# design.net
KiCad netlist of a schematic drawn in Altium Designer
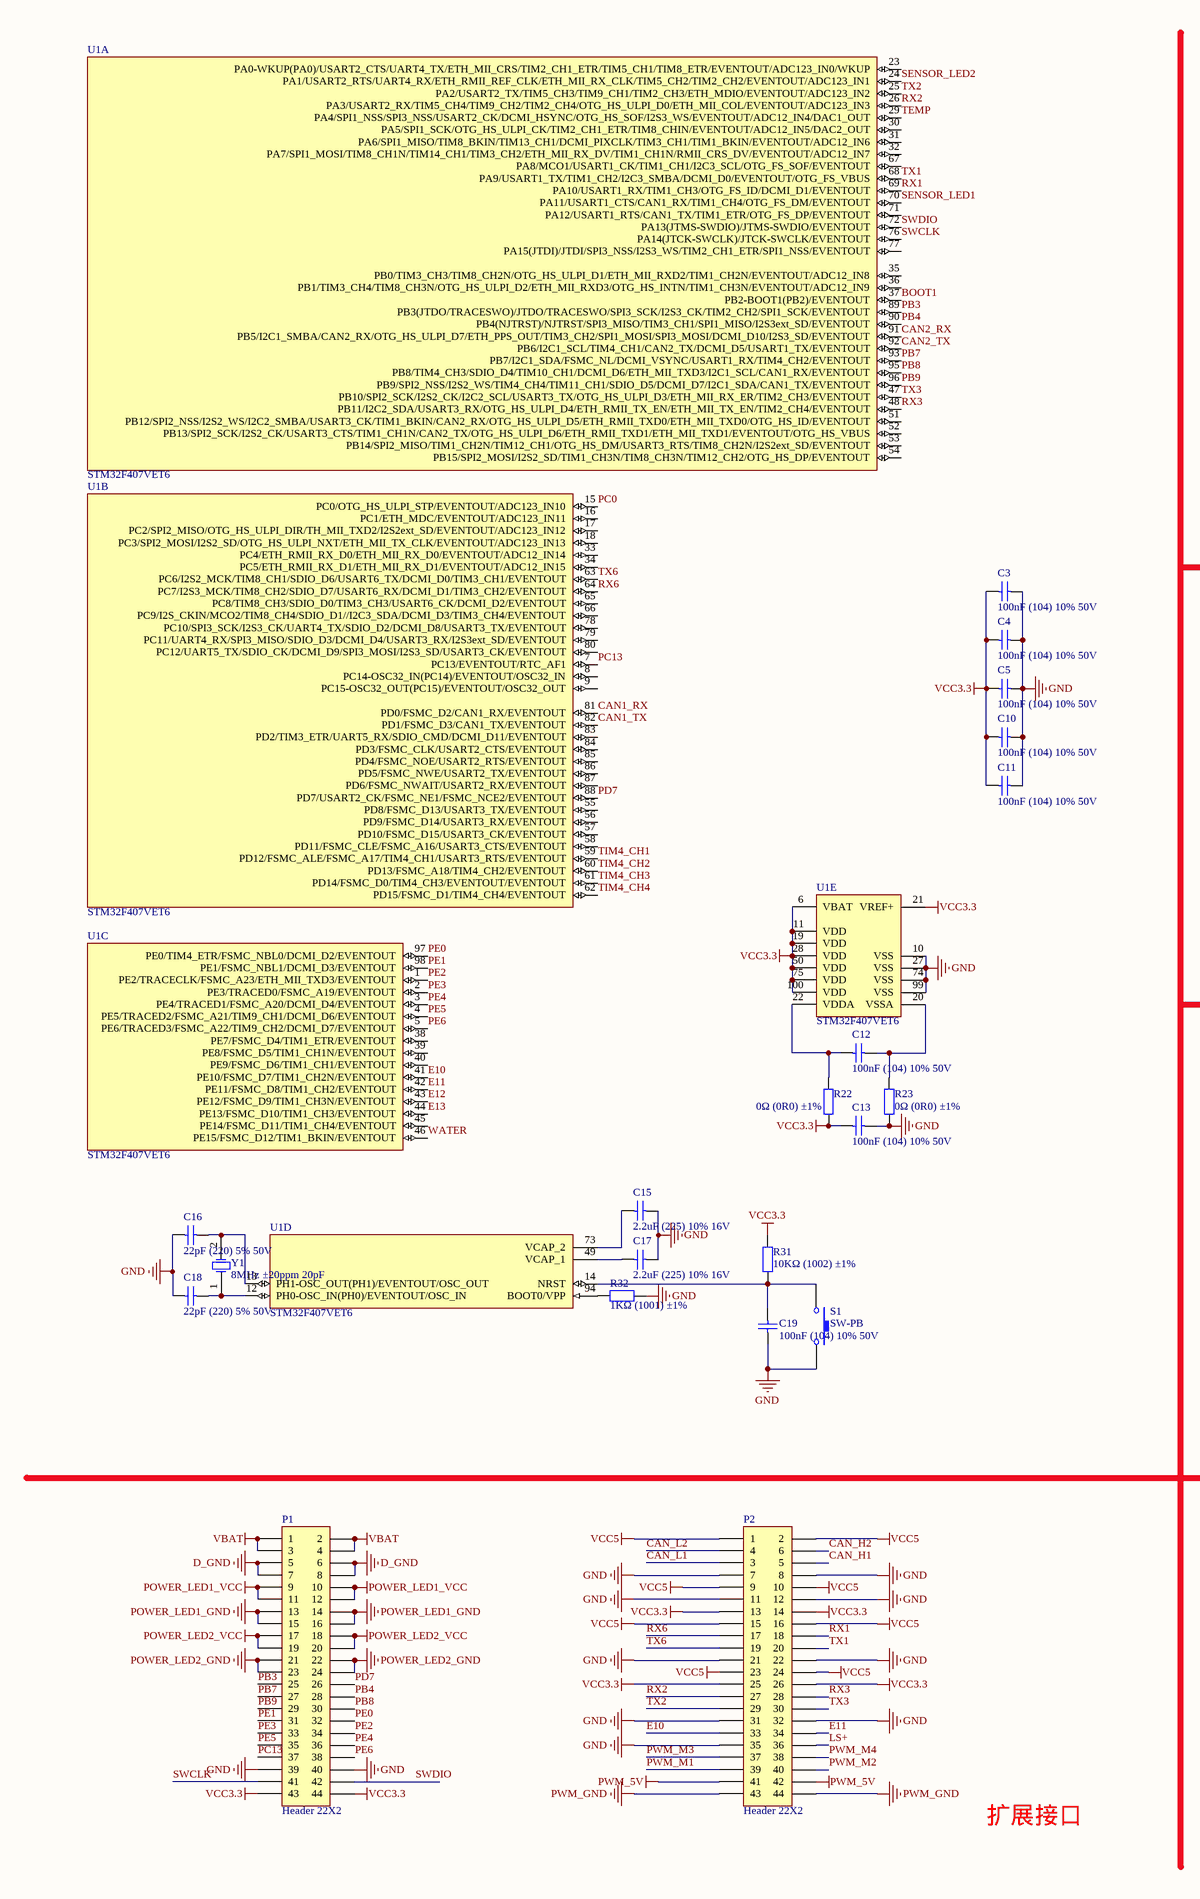
[diagram p0: 主控板.SchDoc, left]
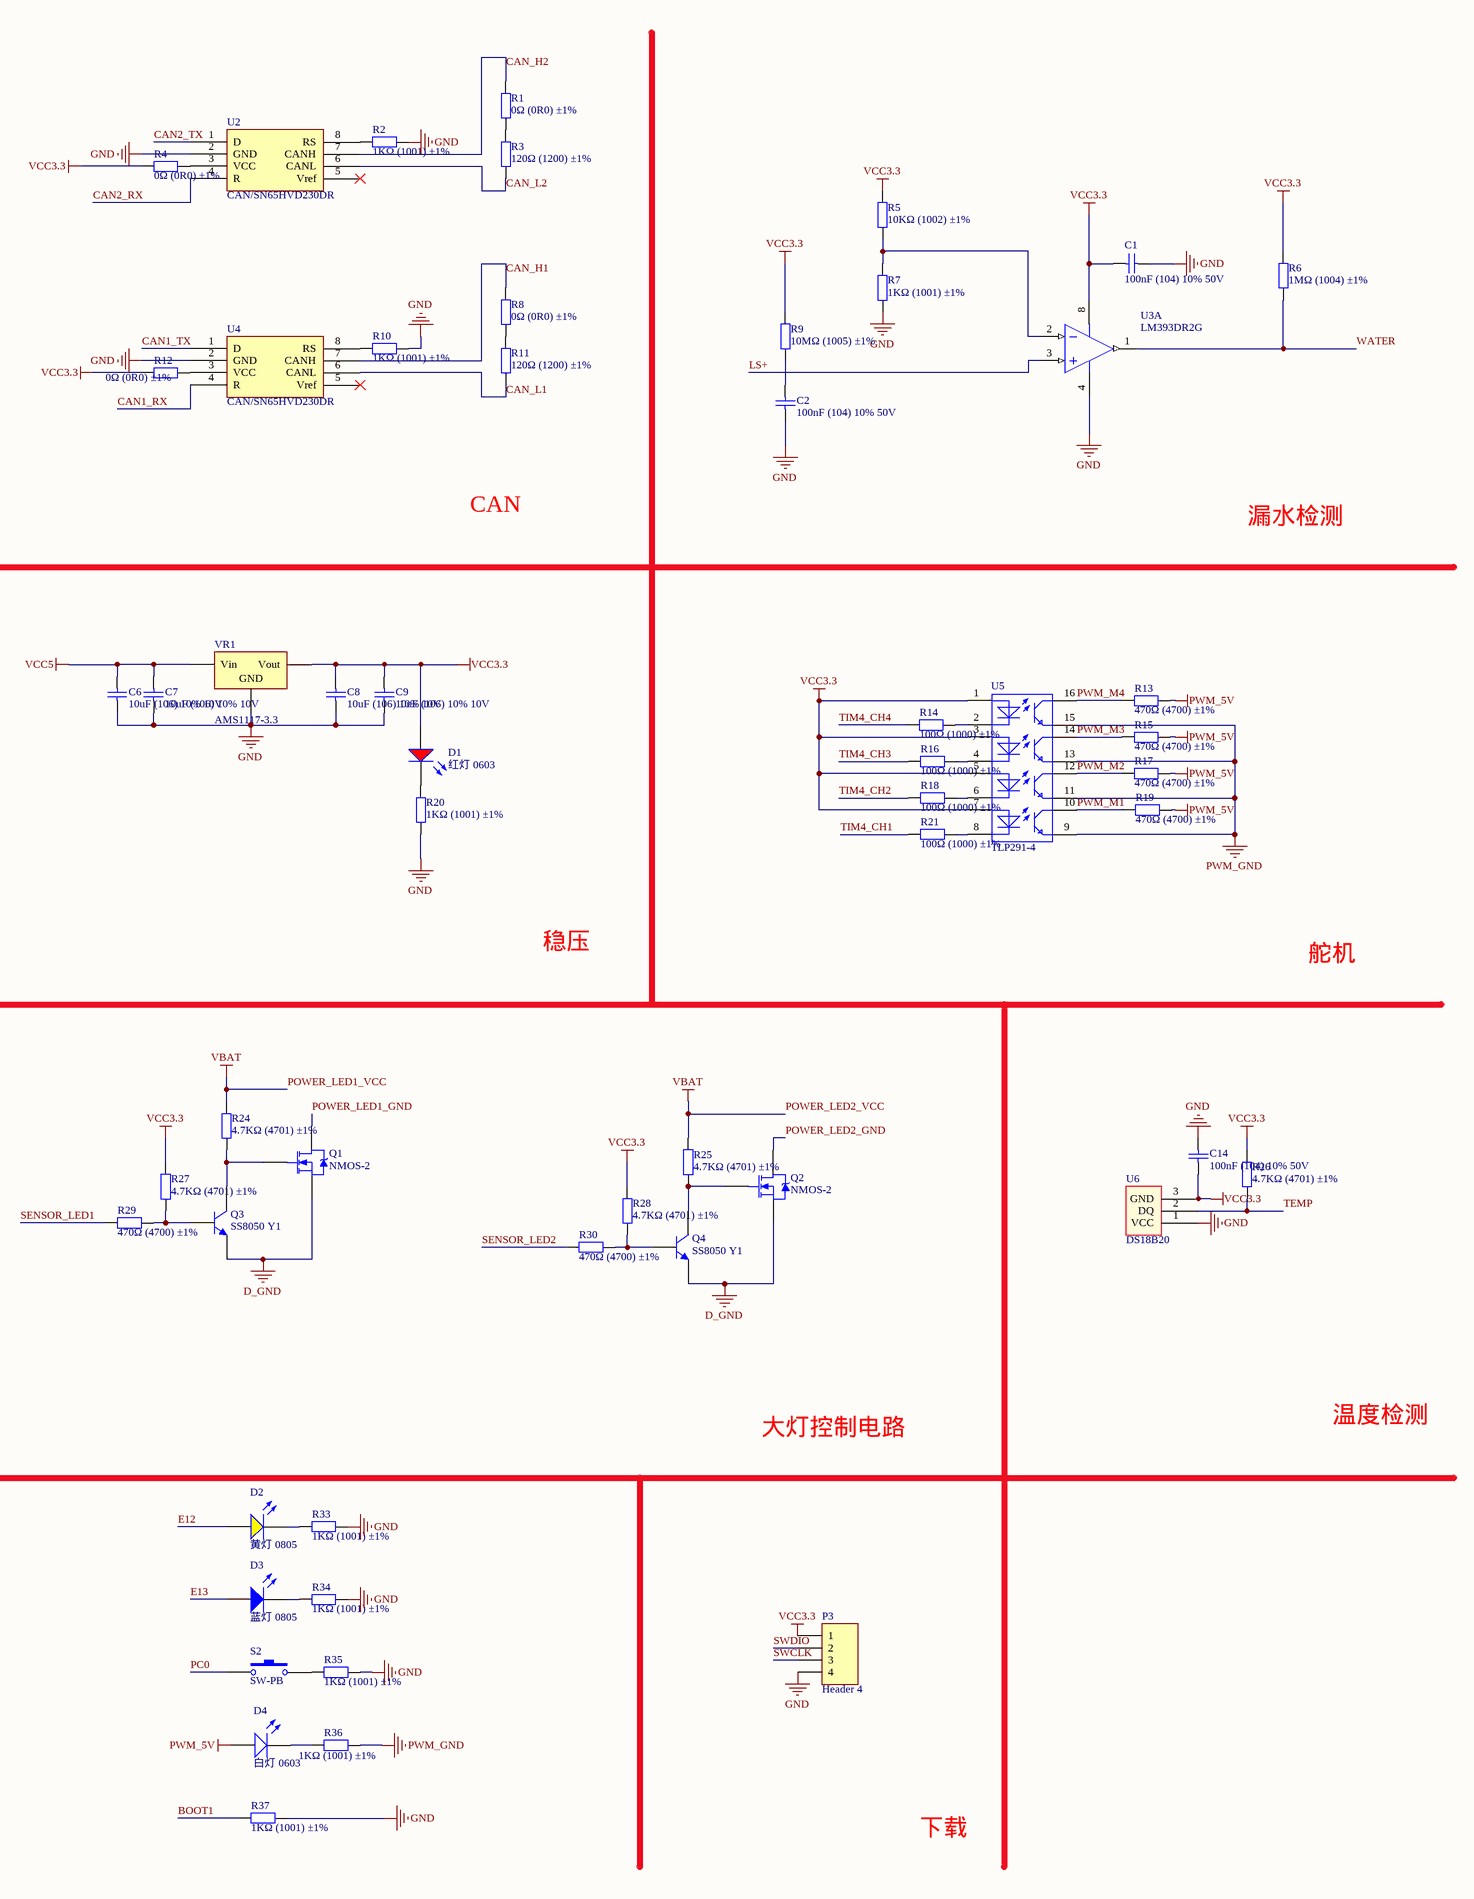
[diagram p1: 主控板.SchDoc, right]

(export (version "E")
  (design (tool "Eeschema 10.0.6"))
  (components
    (comp (ref "C1")
      (value "100nF (104) 10% 50V")
      (footprint "0603_C")
      (description "贴片电容")
      (libsource (lib "Miscellaneous Devices LC") (part "0603 100nF (104) 10% 50V"))
    )
    (comp (ref "C2")
      (value "100nF (104) 10% 50V")
      (footprint "0603_C")
      (description "贴片电容")
      (libsource (lib "Miscellaneous Devices LC") (part "0603 100nF (104) 10% 50V"))
    )
    (comp (ref "C3")
      (value "100nF (104) 10% 50V")
      (footprint "0603_C")
      (description "贴片电容")
      (libsource (lib "Miscellaneous Devices LC") (part "0603 100nF (104) 10% 50V"))
    )
    (comp (ref "C4")
      (value "100nF (104) 10% 50V")
      (footprint "0603_C")
      (description "贴片电容")
      (libsource (lib "Miscellaneous Devices LC") (part "0603 100nF (104) 10% 50V"))
    )
    (comp (ref "C5")
      (value "100nF (104) 10% 50V")
      (footprint "0603_C")
      (description "贴片电容")
      (libsource (lib "Miscellaneous Devices LC") (part "0603 100nF (104) 10% 50V"))
    )
    (comp (ref "C6")
      (value "10uF (106) 10% 10V")
      (footprint "0603_C")
      (description "贴片电容")
      (libsource (lib "Miscellaneous Devices LC") (part "0603 10uF (106) 10% 10V"))
    )
    (comp (ref "C7")
      (value "10uF (106) 10% 10V")
      (footprint "0603_C")
      (description "贴片电容")
      (libsource (lib "Miscellaneous Devices LC") (part "0603 10uF (106) 10% 10V"))
    )
    (comp (ref "C8")
      (value "10uF (106) 10% 10V")
      (footprint "0603_C")
      (description "贴片电容")
      (libsource (lib "Miscellaneous Devices LC") (part "0603 10uF (106) 10% 10V"))
    )
    (comp (ref "C9")
      (value "10uF (106) 10% 10V")
      (footprint "0603_C")
      (description "贴片电容")
      (libsource (lib "Miscellaneous Devices LC") (part "0603 10uF (106) 10% 10V"))
    )
    (comp (ref "C10")
      (value "100nF (104) 10% 50V")
      (footprint "0603_C")
      (description "贴片电容")
      (libsource (lib "Miscellaneous Devices LC") (part "0603 100nF (104) 10% 50V"))
    )
    (comp (ref "C11")
      (value "100nF (104) 10% 50V")
      (footprint "0603_C")
      (description "贴片电容")
      (libsource (lib "Miscellaneous Devices LC") (part "0603 100nF (104) 10% 50V"))
    )
    (comp (ref "C12")
      (value "100nF (104) 10% 50V")
      (footprint "0603_C")
      (description "贴片电容")
      (libsource (lib "Miscellaneous Devices LC") (part "0603 100nF (104) 10% 50V"))
    )
    (comp (ref "C13")
      (value "100nF (104) 10% 50V")
      (footprint "0603_C")
      (description "贴片电容")
      (libsource (lib "Miscellaneous Devices LC") (part "0603 100nF (104) 10% 50V"))
    )
    (comp (ref "C14")
      (value "100nF (104) 10% 50V")
      (footprint "0603_C")
      (description "贴片电容")
      (libsource (lib "Miscellaneous Devices LC") (part "0603 100nF (104) 10% 50V"))
    )
    (comp (ref "C15")
      (value "2.2uF (225) 10% 16V")
      (footprint "0603_C")
      (description "贴片电容")
      (libsource (lib "Miscellaneous Devices LC") (part "0603 2.2uF (225) 10% 16V"))
    )
    (comp (ref "C16")
      (value "22pF (220) 5% 50V")
      (footprint "0603_C")
      (description "贴片电容")
      (libsource (lib "Miscellaneous Devices LC") (part "0603 22pF (220) 5% 50V"))
    )
    (comp (ref "C17")
      (value "2.2uF (225) 10% 16V")
      (footprint "0603_C")
      (description "贴片电容")
      (libsource (lib "Miscellaneous Devices LC") (part "0603 2.2uF (225) 10% 16V"))
    )
    (comp (ref "C18")
      (value "22pF (220) 5% 50V")
      (footprint "0603_C")
      (description "贴片电容")
      (libsource (lib "Miscellaneous Devices LC") (part "0603 22pF (220) 5% 50V"))
    )
    (comp (ref "C19")
      (value "100nF (104) 10% 50V")
      (footprint "0603_C")
      (description "贴片电容")
      (libsource (lib "Miscellaneous Devices LC") (part "0603 100nF (104) 10% 50V"))
    )
    (comp (ref "D1")
      (value "红灯 0603")
      (footprint "0603_LED_S1")
      (description "发光二极管")
      (libsource (lib "Miscellaneous Devices LC") (part "0603 红灯"))
    )
    (comp (ref "D2")
      (value "黄灯 0805")
      (footprint "0805_LED_S1")
      (description "发光二极管")
      (libsource (lib "Miscellaneous Devices LC") (part "0805 黄灯"))
    )
    (comp (ref "D3")
      (value "蓝灯 0805")
      (footprint "0805_LED_S1")
      (description "发光二极管")
      (libsource (lib "Miscellaneous Devices LC") (part "0805 蓝灯"))
    )
    (comp (ref "D4")
      (value "白灯 0603")
      (footprint "0603_LED_S1")
      (description "发光二极管")
      (libsource (lib "Miscellaneous Devices LC") (part "0603 白灯"))
    )
    (comp (ref "P1")
      (value "Header 22X2")
      (footprint "HDR2X22")
      (description "Header, 22-Pin, Dual row")
      (fields (field (name "PUBLISHER") "Altium Limited"))
      (libsource (lib "") (part "Header 22X2_1"))
    )
    (comp (ref "P2")
      (value "Header 22X2")
      (footprint "HDR2X22")
      (description "Header, 22-Pin, Dual row")
      (fields (field (name "PUBLISHER") "Altium Limited"))
      (libsource (lib "Miscellaneous Connectors") (part "Header 22X2"))
    )
    (comp (ref "P3")
      (value "Header 4")
      (footprint "Molex-4")
      (description "Header, 4-Pin")
      (fields (field (name "PUBLISHER") "Altium Limited"))
      (libsource (lib "ZSJ") (part "Header 4_1"))
    )
    (comp (ref "Q1")
      (value "NMOS-2")
      (footprint "TO-252")
      (description "N-Channel Power MOSFET")
      (fields (field (name "PUBLISHER") "Altium Limited"))
      (libsource (lib "ZSJ") (part "NMOS-2"))
    )
    (comp (ref "Q2")
      (value "NMOS-2")
      (footprint "TO-252")
      (description "N-Channel Power MOSFET")
      (fields (field (name "PUBLISHER") "Altium Limited"))
      (libsource (lib "ZSJ") (part "NMOS-2"))
    )
    (comp (ref "Q3")
      (value "SS8050 Y1")
      (footprint "SOT-23(SOT-23-3)")
      (description "三极管")
      (libsource (lib "Miscellaneous Devices LC") (part "SOT-23 SS8050 Y1"))
    )
    (comp (ref "Q4")
      (value "SS8050 Y1")
      (footprint "SOT-23(SOT-23-3)")
      (description "三极管")
      (libsource (lib "Miscellaneous Devices LC") (part "SOT-23 SS8050 Y1"))
    )
    (comp (ref "R1")
      (value "0Ω (0R0) ±1%")
      (footprint "0603_R")
      (description "贴片电阻")
      (libsource (lib "") (part "0603 0Ω (0R0) 1%_1"))
    )
    (comp (ref "R2")
      (value "1KΩ (1001) ±1%")
      (footprint "0603_R")
      (description "贴片电阻")
      (libsource (lib "Miscellaneous Devices LC") (part "0603 1KΩ (1001) 1%"))
    )
    (comp (ref "R3")
      (value "120Ω (1200) ±1%")
      (footprint "0603_R")
      (description "贴片电阻")
      (libsource (lib "Miscellaneous Devices LC") (part "0603 120Ω (1200) 1%"))
    )
    (comp (ref "R4")
      (value "0Ω (0R0) ±1%")
      (footprint "0603_R")
      (description "贴片电阻")
      (libsource (lib "Miscellaneous Devices LC") (part "0603 0Ω (0R0) 1%"))
    )
    (comp (ref "R5")
      (value "10KΩ (1002) ±1%")
      (footprint "0603_R")
      (description "贴片电阻")
      (libsource (lib "Miscellaneous Devices LC") (part "0603 10KΩ (1002) 1%"))
    )
    (comp (ref "R6")
      (value "1MΩ (1004) ±1%")
      (footprint "0603_R")
      (description "贴片电阻")
      (libsource (lib "Miscellaneous Devices LC") (part "0603 1MΩ (1004) 1%"))
    )
    (comp (ref "R7")
      (value "1KΩ (1001) ±1%")
      (footprint "0603_R")
      (description "贴片电阻")
      (libsource (lib "") (part "0603 1KΩ (1001) 1%_1"))
    )
    (comp (ref "R8")
      (value "0Ω (0R0) ±1%")
      (footprint "0603_R")
      (description "贴片电阻")
      (libsource (lib "") (part "0603 0Ω (0R0) 1%_1"))
    )
    (comp (ref "R9")
      (value "10MΩ (1005) ±1%")
      (footprint "0603_R")
      (description "贴片电阻")
      (libsource (lib "Miscellaneous Devices LC") (part "0603 10MΩ (1005) 1%"))
    )
    (comp (ref "R10")
      (value "1KΩ (1001) ±1%")
      (footprint "0603_R")
      (description "贴片电阻")
      (libsource (lib "Miscellaneous Devices LC") (part "0603 1KΩ (1001) 1%"))
    )
    (comp (ref "R11")
      (value "120Ω (1200) ±1%")
      (footprint "0603_R")
      (description "贴片电阻")
      (libsource (lib "Miscellaneous Devices LC") (part "0603 120Ω (1200) 1%"))
    )
    (comp (ref "R12")
      (value "0Ω (0R0) ±1%")
      (footprint "0603_R")
      (description "贴片电阻")
      (libsource (lib "Miscellaneous Devices LC") (part "0603 0Ω (0R0) 1%"))
    )
    (comp (ref "R13")
      (value "470Ω (4700) ±1%")
      (footprint "0603_R")
      (description "贴片电阻")
      (libsource (lib "Miscellaneous Devices LC") (part "0603 470Ω (4700) 1%"))
    )
    (comp (ref "R14")
      (value "100Ω (1000) ±1%")
      (footprint "0603_R")
      (description "贴片电阻")
      (libsource (lib "Miscellaneous Devices LC") (part "0603 100Ω (1000) 1%"))
    )
    (comp (ref "R15")
      (value "470Ω (4700) ±1%")
      (footprint "0603_R")
      (description "贴片电阻")
      (libsource (lib "Miscellaneous Devices LC") (part "0603 470Ω (4700) 1%"))
    )
    (comp (ref "R16")
      (value "100Ω (1000) ±1%")
      (footprint "0603_R")
      (description "贴片电阻")
      (libsource (lib "Miscellaneous Devices LC") (part "0603 100Ω (1000) 1%"))
    )
    (comp (ref "R17")
      (value "470Ω (4700) ±1%")
      (footprint "0603_R")
      (description "贴片电阻")
      (libsource (lib "Miscellaneous Devices LC") (part "0603 470Ω (4700) 1%"))
    )
    (comp (ref "R18")
      (value "100Ω (1000) ±1%")
      (footprint "0603_R")
      (description "贴片电阻")
      (libsource (lib "Miscellaneous Devices LC") (part "0603 100Ω (1000) 1%"))
    )
    (comp (ref "R19")
      (value "470Ω (4700) ±1%")
      (footprint "0603_R")
      (description "贴片电阻")
      (libsource (lib "Miscellaneous Devices LC") (part "0603 470Ω (4700) 1%"))
    )
    (comp (ref "R20")
      (value "1KΩ (1001) ±1%")
      (footprint "0603_R")
      (description "贴片电阻")
      (libsource (lib "") (part "0603 1KΩ (1001) 1%_1"))
    )
    (comp (ref "R21")
      (value "100Ω (1000) ±1%")
      (footprint "0603_R")
      (description "贴片电阻")
      (libsource (lib "Miscellaneous Devices LC") (part "0603 100Ω (1000) 1%"))
    )
    (comp (ref "R22")
      (value "0Ω (0R0) ±1%")
      (footprint "0603_R")
      (description "贴片电阻")
      (libsource (lib "") (part "0603 0Ω (0R0) 1%_1"))
    )
    (comp (ref "R23")
      (value "0Ω (0R0) ±1%")
      (footprint "0603_R")
      (description "贴片电阻")
      (libsource (lib "") (part "0603 0Ω (0R0) 1%_1"))
    )
    (comp (ref "R24")
      (value "4.7KΩ (4701) ±1%")
      (footprint "0603_R")
      (description "贴片电阻")
      (libsource (lib "Miscellaneous Devices LC") (part "0603 4.7KΩ (4701) 1%"))
    )
    (comp (ref "R25")
      (value "4.7KΩ (4701) ±1%")
      (footprint "0603_R")
      (description "贴片电阻")
      (libsource (lib "Miscellaneous Devices LC") (part "0603 4.7KΩ (4701) 1%"))
    )
    (comp (ref "R26")
      (value "4.7KΩ (4701) ±1%")
      (footprint "0603_R")
      (description "贴片电阻")
      (libsource (lib "Miscellaneous Devices LC") (part "0603 4.7KΩ (4701) 1%"))
    )
    (comp (ref "R27")
      (value "4.7KΩ (4701) ±1%")
      (footprint "0603_R")
      (description "贴片电阻")
      (libsource (lib "Miscellaneous Devices LC") (part "0603 4.7KΩ (4701) 1%"))
    )
    (comp (ref "R28")
      (value "4.7KΩ (4701) ±1%")
      (footprint "0603_R")
      (description "贴片电阻")
      (libsource (lib "Miscellaneous Devices LC") (part "0603 4.7KΩ (4701) 1%"))
    )
    (comp (ref "R29")
      (value "470Ω (4700) ±1%")
      (footprint "0603_R")
      (description "贴片电阻")
      (libsource (lib "Miscellaneous Devices LC") (part "0603 470Ω (4700) 1%"))
    )
    (comp (ref "R30")
      (value "470Ω (4700) ±1%")
      (footprint "0603_R")
      (description "贴片电阻")
      (libsource (lib "Miscellaneous Devices LC") (part "0603 470Ω (4700) 1%"))
    )
    (comp (ref "R31")
      (value "10KΩ (1002) ±1%")
      (footprint "0603_R")
      (description "贴片电阻")
      (libsource (lib "Miscellaneous Devices LC") (part "0603 10KΩ (1002) 1%"))
    )
    (comp (ref "R32")
      (value "1KΩ (1001) ±1%")
      (footprint "0603_R")
      (description "贴片电阻")
      (libsource (lib "Miscellaneous Devices LC") (part "0603 1KΩ (1001) 1%"))
    )
    (comp (ref "R33")
      (value "1KΩ (1001) ±1%")
      (footprint "0603_R")
      (description "贴片电阻")
      (libsource (lib "Miscellaneous Devices LC") (part "0603 1KΩ (1001) 1%"))
    )
    (comp (ref "R34")
      (value "1KΩ (1001) ±1%")
      (footprint "0603_R")
      (description "贴片电阻")
      (libsource (lib "Miscellaneous Devices LC") (part "0603 1KΩ (1001) 1%"))
    )
    (comp (ref "R35")
      (value "1KΩ (1001) ±1%")
      (footprint "0603_R")
      (description "贴片电阻")
      (libsource (lib "Miscellaneous Devices LC") (part "0603 1KΩ (1001) 1%"))
    )
    (comp (ref "R36")
      (value "1KΩ (1001) ±1%")
      (footprint "0603_R")
      (description "贴片电阻")
      (libsource (lib "") (part "0603 1KΩ (1001) 1%_2"))
    )
    (comp (ref "R37")
      (value "1KΩ (1001) ±1%")
      (footprint "0603_R")
      (description "贴片电阻")
      (libsource (lib "Miscellaneous Devices LC") (part "0603 1KΩ (1001) 1%"))
    )
    (comp (ref "S1")
      (value "SW-PB")
      (footprint "贴片按键")
      (description "Switch")
      (fields (field (name "PUBLISHER") "Altium Limited"))
      (libsource (lib "ZSJ") (part "SW-PB"))
    )
    (comp (ref "S2")
      (value "SW-PB")
      (footprint "贴片按键")
      (description "Switch")
      (fields (field (name "PUBLISHER") "Altium Limited"))
      (libsource (lib "ZSJ") (part "SW-PB"))
    )
    (comp (ref "U1")
      (value "STM32F407VET6")
      (footprint "LQFP-100_14x14x05P")
      (description "ARM")
      (libsource (lib "Miscellaneous Devices LC") (part "STM32F407VET6"))
    )
    (comp (ref "U2")
      (value "CAN/SN65HVD230DR")
      (footprint "SOIC-8_150mil")
      (description "CAN")
      (libsource (lib "Miscellaneous Devices LC") (part "CAN/SN65HVD230DR_[C12084]"))
    )
    (comp (ref "U3")
      (value "LM393DR2G")
      (footprint "SOIC-8_150mil")
      (description "电压比较器")
      (libsource (lib "Miscellaneous Devices LC") (part "LM393DR2G_[C7955]"))
    )
    (comp (ref "U4")
      (value "CAN/SN65HVD230DR")
      (footprint "SOIC-8_150mil")
      (description "CAN")
      (libsource (lib "Miscellaneous Devices LC") (part "CAN/SN65HVD230DR_[C12084]"))
    )
    (comp (ref "U5")
      (value "TLP291-4")
      (footprint "LC-SOP-16_150mil")
      (libsource (lib "ZSJ") (part "TLP521-4"))
    )
    (comp (ref "U6") (value "DS18B20") (footprint "TO-92A") (libsource (lib "ZSJ") (part "DS18B20")))
    (comp (ref "VR1")
      (value "AMS1117-3.3")
      (footprint "SOT-223")
      (description "低压差线性稳压(LDO)")
      (libsource (lib "Miscellaneous Devices LC") (part "SOT-223 AMS1117-3.3"))
    )
    (comp (ref "Y1")
      (value "8MHz ±20ppm 20pF")
      (footprint "SMD-5032_2P")
      (description "贴片晶振")
      (libsource (lib "Miscellaneous Devices LC") (part "SMD-5032_2P 8MHz 20ppm 20pF"))
    )
  )
  (nets
    (net (code "1") (name "/BOOT1") (class "Default")
      (node (ref "R37") (pin "1") (pinfunction "1_1") (pintype "passive"))
      (node (ref "U1") (pin "37") (pinfunction "PB2-BOOT1(PB2)/EVENTOUT_37") (pintype "bidirectional"))
    )
    (net (code "2") (name "/CAN1_RX") (class "Default")
      (node (ref "U1") (pin "81") (pinfunction "PD0/FSMC_D2/CAN1_RX/EVENTOUT_81") (pintype "bidirectional"))
      (node (ref "U4") (pin "4") (pinfunction "R_4") (pintype "passive"))
    )
    (net (code "3") (name "/CAN1_TX") (class "Default")
      (node (ref "U1") (pin "82") (pinfunction "PD1/FSMC_D3/CAN1_TX/EVENTOUT_82") (pintype "bidirectional"))
      (node (ref "U4") (pin "1") (pinfunction "D_1") (pintype "passive"))
    )
    (net (code "4") (name "/CAN2_RX") (class "Default")
      (node (ref "U1") (pin "91") (pinfunction "PB5/I2C1_SMBA/CAN2_RX/OTG_HS_ULPI_D7/ETH_PPS_OUT/TIM3_CH2/SPI1_MOSI/SPI3_MOSI/DCMI_D10/I2S3_SD/EVENTOUT_91") (pintype "bidirectional"))
      (node (ref "U2") (pin "4") (pinfunction "R_4") (pintype "passive"))
    )
    (net (code "5") (name "/CAN2_TX") (class "Default")
      (node (ref "U1") (pin "92") (pinfunction "PB6/I2C1_SCL/TIM4_CH1/CAN2_TX/DCMI_D5/USART1_TX/EVENTOUT_92") (pintype "bidirectional"))
      (node (ref "U2") (pin "1") (pinfunction "D_1") (pintype "passive"))
    )
    (net (code "6") (name "/CAN_H1") (class "Default")
      (node (ref "P2") (pin "5") (pinfunction "5_5") (pintype "passive"))
      (node (ref "R8") (pin "2") (pinfunction "2_2") (pintype "passive"))
      (node (ref "U4") (pin "7") (pinfunction "CANH_7") (pintype "passive"))
    )
    (net (code "7") (name "/CAN_H2") (class "Default")
      (node (ref "P2") (pin "6") (pinfunction "6_6") (pintype "passive"))
      (node (ref "R1") (pin "2") (pinfunction "2_2") (pintype "passive"))
      (node (ref "U2") (pin "7") (pinfunction "CANH_7") (pintype "passive"))
    )
    (net (code "8") (name "/CAN_L1") (class "Default")
      (node (ref "P2") (pin "3") (pinfunction "3_3") (pintype "passive"))
      (node (ref "R11") (pin "1") (pinfunction "1_1") (pintype "passive"))
      (node (ref "U4") (pin "6") (pinfunction "CANL_6") (pintype "passive"))
    )
    (net (code "9") (name "/CAN_L2") (class "Default")
      (node (ref "P2") (pin "4") (pinfunction "4_4") (pintype "passive"))
      (node (ref "R3") (pin "1") (pinfunction "1_1") (pintype "passive"))
      (node (ref "U2") (pin "6") (pinfunction "CANL_6") (pintype "passive"))
    )
    (net (code "10") (name "/E10") (class "Default")
      (node (ref "P2") (pin "33") (pinfunction "33_33") (pintype "passive"))
      (node (ref "U1") (pin "41") (pinfunction "PE10/FSMC_D7/TIM1_CH2N/EVENTOUT_41") (pintype "bidirectional"))
    )
    (net (code "11") (name "/E11") (class "Default")
      (node (ref "P2") (pin "34") (pinfunction "34_34") (pintype "passive"))
      (node (ref "U1") (pin "42") (pinfunction "PE11/FSMC_D8/TIM1_CH2/EVENTOUT_42") (pintype "bidirectional"))
    )
    (net (code "12") (name "/E12") (class "Default")
      (node (ref "D2") (pin "A") (pinfunction "A_A") (pintype "passive"))
      (node (ref "U1") (pin "43") (pinfunction "PE12/FSMC_D9/TIM1_CH3N/EVENTOUT_43") (pintype "bidirectional"))
    )
    (net (code "13") (name "/E13") (class "Default")
      (node (ref "D3") (pin "A") (pinfunction "A_A") (pintype "passive"))
      (node (ref "U1") (pin "44") (pinfunction "PE13/FSMC_D10/TIM1_CH3/EVENTOUT_44") (pintype "bidirectional"))
    )
    (net (code "14") (name "/LS+") (class "Default")
      (node (ref "P2") (pin "36") (pinfunction "36_36") (pintype "passive"))
      (node (ref "U3") (pin "3") (pinfunction "IN+_3") (pintype "input"))
    )
    (net (code "15") (name "/PB3") (class "Default")
      (node (ref "P1") (pin "25") (pinfunction "25_25") (pintype "passive"))
      (node (ref "U1") (pin "89") (pinfunction "PB3(JTDO/TRACESWO)/JTDO/TRACESWO/SPI3_SCK/I2S3_CK/TIM2_CH2/SPI1_SCK/EVENTOUT_89") (pintype "bidirectional"))
    )
    (net (code "16") (name "/PB4") (class "Default")
      (node (ref "P1") (pin "28") (pinfunction "28_28") (pintype "passive"))
      (node (ref "U1") (pin "90") (pinfunction "PB4(NJTRST)/NJTRST/SPI3_MISO/TIM3_CH1/SPI1_MISO/I2S3ext_SD/EVENTOUT_90") (pintype "bidirectional"))
    )
    (net (code "17") (name "/PB7") (class "Default")
      (node (ref "P1") (pin "27") (pinfunction "27_27") (pintype "passive"))
      (node (ref "U1") (pin "93") (pinfunction "PB7/I2C1_SDA/FSMC_NL/DCMI_VSYNC/USART1_RX/TIM4_CH2/EVENTOUT_93") (pintype "bidirectional"))
    )
    (net (code "18") (name "/PB8") (class "Default")
      (node (ref "P1") (pin "30") (pinfunction "30_30") (pintype "passive"))
      (node (ref "U1") (pin "95") (pinfunction "PB8/TIM4_CH3/SDIO_D4/TIM10_CH1/DCMI_D6/ETH_MII_TXD3/I2C1_SCL/CAN1_RX/EVENTOUT_95") (pintype "bidirectional"))
    )
    (net (code "19") (name "/PB9") (class "Default")
      (node (ref "P1") (pin "29") (pinfunction "29_29") (pintype "passive"))
      (node (ref "U1") (pin "96") (pinfunction "PB9/SPI2_NSS/I2S2_WS/TIM4_CH4/TIM11_CH1/SDIO_D5/DCMI_D7/I2C1_SDA/CAN1_TX/EVENTOUT_96") (pintype "bidirectional"))
    )
    (net (code "20") (name "/PC0") (class "Default")
      (node (ref "S2") (pin "1") (pinfunction "1_1") (pintype "passive"))
      (node (ref "U1") (pin "15") (pinfunction "PC0/OTG_HS_ULPI_STP/EVENTOUT/ADC123_IN10_15") (pintype "bidirectional"))
    )
    (net (code "21") (name "/PC13") (class "Default")
      (node (ref "P1") (pin "37") (pinfunction "37_37") (pintype "passive"))
      (node (ref "U1") (pin "7") (pinfunction "PC13/EVENTOUT/RTC_AF1_7") (pintype "bidirectional"))
    )
    (net (code "22") (name "/PD7") (class "Default")
      (node (ref "P1") (pin "26") (pinfunction "26_26") (pintype "passive"))
      (node (ref "U1") (pin "88") (pinfunction "PD7/USART2_CK/FSMC_NE1/FSMC_NCE2/EVENTOUT_88") (pintype "bidirectional"))
    )
    (net (code "23") (name "/PE0") (class "Default")
      (node (ref "P1") (pin "32") (pinfunction "32_32") (pintype "passive"))
      (node (ref "U1") (pin "97") (pinfunction "PE0/TIM4_ETR/FSMC_NBL0/DCMI_D2/EVENTOUT_97") (pintype "bidirectional"))
    )
    (net (code "24") (name "/PE1") (class "Default")
      (node (ref "P1") (pin "31") (pinfunction "31_31") (pintype "passive"))
      (node (ref "U1") (pin "98") (pinfunction "PE1/FSMC_NBL1/DCMI_D3/EVENTOUT_98") (pintype "bidirectional"))
    )
    (net (code "25") (name "/PE2") (class "Default")
      (node (ref "P1") (pin "34") (pinfunction "34_34") (pintype "passive"))
      (node (ref "U1") (pin "1") (pinfunction "PE2/TRACECLK/FSMC_A23/ETH_MII_TXD3/EVENTOUT_1") (pintype "bidirectional"))
    )
    (net (code "26") (name "/PE3") (class "Default")
      (node (ref "P1") (pin "33") (pinfunction "33_33") (pintype "passive"))
      (node (ref "U1") (pin "2") (pinfunction "PE3/TRACED0/FSMC_A19/EVENTOUT_2") (pintype "bidirectional"))
    )
    (net (code "27") (name "/PE4") (class "Default")
      (node (ref "P1") (pin "36") (pinfunction "36_36") (pintype "passive"))
      (node (ref "U1") (pin "3") (pinfunction "PE4/TRACED1/FSMC_A20/DCMI_D4/EVENTOUT_3") (pintype "bidirectional"))
    )
    (net (code "28") (name "/PE5") (class "Default")
      (node (ref "P1") (pin "35") (pinfunction "35_35") (pintype "passive"))
      (node (ref "U1") (pin "4") (pinfunction "PE5/TRACED2/FSMC_A21/TIM9_CH1/DCMI_D6/EVENTOUT_4") (pintype "bidirectional"))
    )
    (net (code "29") (name "/PE6") (class "Default")
      (node (ref "P1") (pin "38") (pinfunction "38_38") (pintype "passive"))
      (node (ref "U1") (pin "5") (pinfunction "PE6/TRACED3/FSMC_A22/TIM9_CH2/DCMI_D7/EVENTOUT_5") (pintype "bidirectional"))
    )
    (net (code "30") (name "/PWM_M1") (class "Default")
      (node (ref "P2") (pin "39") (pinfunction "39_39") (pintype "passive"))
      (node (ref "R19") (pin "1") (pinfunction "1_1") (pintype "passive"))
      (node (ref "U5") (pin "10") (pinfunction "10_10") (pintype "passive"))
    )
    (net (code "31") (name "/PWM_M2") (class "Default")
      (node (ref "P2") (pin "40") (pinfunction "40_40") (pintype "passive"))
      (node (ref "R17") (pin "1") (pinfunction "1_1") (pintype "passive"))
      (node (ref "U5") (pin "12") (pinfunction "12_12") (pintype "passive"))
    )
    (net (code "32") (name "/PWM_M3") (class "Default")
      (node (ref "P2") (pin "37") (pinfunction "37_37") (pintype "passive"))
      (node (ref "R15") (pin "1") (pinfunction "1_1") (pintype "passive"))
      (node (ref "U5") (pin "14") (pinfunction "14_14") (pintype "passive"))
    )
    (net (code "33") (name "/PWM_M4") (class "Default")
      (node (ref "P2") (pin "38") (pinfunction "38_38") (pintype "passive"))
      (node (ref "R13") (pin "1") (pinfunction "1_1") (pintype "passive"))
      (node (ref "U5") (pin "16") (pinfunction "16_16") (pintype "passive"))
    )
    (net (code "34") (name "/RX1") (class "Default")
      (node (ref "P2") (pin "18") (pinfunction "18_18") (pintype "passive"))
      (node (ref "U1") (pin "69") (pinfunction "PA10/USART1_RX/TIM1_CH3/OTG_FS_ID/DCMI_D1/EVENTOUT_69") (pintype "bidirectional"))
    )
    (net (code "35") (name "/RX2") (class "Default")
      (node (ref "P2") (pin "27") (pinfunction "27_27") (pintype "passive"))
      (node (ref "U1") (pin "26") (pinfunction "PA3/USART2_RX/TIM5_CH4/TIM9_CH2/TIM2_CH4/OTG_HS_ULPI_D0/ETH_MII_COL/EVENTOUT/ADC123_IN3_26") (pintype "bidirectional"))
    )
    (net (code "36") (name "/RX3") (class "Default")
      (node (ref "P2") (pin "28") (pinfunction "28_28") (pintype "passive"))
      (node (ref "U1") (pin "48") (pinfunction "PB11/I2C2_SDA/USART3_RX/OTG_HS_ULPI_D4/ETH_RMII_TX_EN/ETH_MII_TX_EN/TIM2_CH4/EVENTOUT_48") (pintype "bidirectional"))
    )
    (net (code "37") (name "/RX6") (class "Default")
      (node (ref "P2") (pin "17") (pinfunction "17_17") (pintype "passive"))
      (node (ref "U1") (pin "64") (pinfunction "PC7/I2S3_MCK/TIM8_CH2/SDIO_D7/USART6_RX/DCMI_D1/TIM3_CH2/EVENTOUT_64") (pintype "bidirectional"))
    )
    (net (code "38") (name "/SENSOR_LED1") (class "Default")
      (node (ref "R29") (pin "1") (pinfunction "1_1") (pintype "passive"))
      (node (ref "U1") (pin "70") (pinfunction "PA11/USART1_CTS/CAN1_RX/TIM1_CH4/OTG_FS_DM/EVENTOUT_70") (pintype "bidirectional"))
    )
    (net (code "39") (name "/SENSOR_LED2") (class "Default")
      (node (ref "R30") (pin "1") (pinfunction "1_1") (pintype "passive"))
      (node (ref "U1") (pin "24") (pinfunction "PA1/USART2_RTS/UART4_RX/ETH_RMII_REF_CLK/ETH_MII_RX_CLK/TIM5_CH2/TIM2_CH2/EVENTOUT/ADC123_IN1_24") (pintype "bidirectional"))
    )
    (net (code "40") (name "/SWCLK") (class "Default")
      (node (ref "P1") (pin "41") (pinfunction "41_41") (pintype "passive"))
      (node (ref "P3") (pin "3") (pinfunction "3_3") (pintype "passive"))
      (node (ref "U1") (pin "76") (pinfunction "PA14(JTCK-SWCLK)/JTCK-SWCLK/EVENTOUT_76") (pintype "bidirectional"))
    )
    (net (code "41") (name "/SWDIO") (class "Default")
      (node (ref "P1") (pin "42") (pinfunction "42_42") (pintype "passive"))
      (node (ref "P3") (pin "2") (pinfunction "2_2") (pintype "passive"))
      (node (ref "U1") (pin "72") (pinfunction "PA13(JTMS-SWDIO)/JTMS-SWDIO/EVENTOUT_72") (pintype "bidirectional"))
    )
    (net (code "42") (name "/TEMP") (class "Default")
      (node (ref "R26") (pin "1") (pinfunction "1_1") (pintype "passive"))
      (node (ref "U1") (pin "29") (pinfunction "PA4/SPI1_NSS/SPI3_NSS/USART2_CK/DCMI_HSYNC/OTG_HS_SOF/I2S3_WS/EVENTOUT/ADC12_IN4/DAC1_OUT_29") (pintype "bidirectional"))
      (node (ref "U6") (pin "2") (pinfunction "DQ_2") (pintype "passive"))
    )
    (net (code "43") (name "/TIM4_CH1") (class "Default")
      (node (ref "R21") (pin "1") (pinfunction "1_1") (pintype "passive"))
      (node (ref "U1") (pin "59") (pinfunction "PD12/FSMC_ALE/FSMC_A17/TIM4_CH1/USART3_RTS/EVENTOUT_59") (pintype "bidirectional"))
    )
    (net (code "44") (name "/TIM4_CH2") (class "Default")
      (node (ref "R18") (pin "1") (pinfunction "1_1") (pintype "passive"))
      (node (ref "U1") (pin "60") (pinfunction "PD13/FSMC_A18/TIM4_CH2/EVENTOUT_60") (pintype "bidirectional"))
    )
    (net (code "45") (name "/TIM4_CH3") (class "Default")
      (node (ref "R16") (pin "1") (pinfunction "1_1") (pintype "passive"))
      (node (ref "U1") (pin "61") (pinfunction "PD14/FSMC_D0/TIM4_CH3/EVENTOUT/EVENTOUT_61") (pintype "bidirectional"))
    )
    (net (code "46") (name "/TIM4_CH4") (class "Default")
      (node (ref "R14") (pin "1") (pinfunction "1_1") (pintype "passive"))
      (node (ref "U1") (pin "62") (pinfunction "PD15/FSMC_D1/TIM4_CH4/EVENTOUT_62") (pintype "bidirectional"))
    )
    (net (code "47") (name "/TX1") (class "Default")
      (node (ref "P2") (pin "20") (pinfunction "20_20") (pintype "passive"))
      (node (ref "U1") (pin "68") (pinfunction "PA9/USART1_TX/TIM1_CH2/I2C3_SMBA/DCMI_D0/EVENTOUT/OTG_FS_VBUS_68") (pintype "bidirectional"))
    )
    (net (code "48") (name "/TX2") (class "Default")
      (node (ref "P2") (pin "29") (pinfunction "29_29") (pintype "passive"))
      (node (ref "U1") (pin "25") (pinfunction "PA2/USART2_TX/TIM5_CH3/TIM9_CH1/TIM2_CH3/ETH_MDIO/EVENTOUT/ADC123_IN2_25") (pintype "bidirectional"))
    )
    (net (code "49") (name "/TX3") (class "Default")
      (node (ref "P2") (pin "30") (pinfunction "30_30") (pintype "passive"))
      (node (ref "U1") (pin "47") (pinfunction "PB10/SPI2_SCK/I2S2_CK/I2C2_SCL/USART3_TX/OTG_HS_ULPI_D3/ETH_MII_RX_ER/TIM2_CH3/EVENTOUT_47") (pintype "bidirectional"))
    )
    (net (code "50") (name "/TX6") (class "Default")
      (node (ref "P2") (pin "19") (pinfunction "19_19") (pintype "passive"))
      (node (ref "U1") (pin "63") (pinfunction "PC6/I2S2_MCK/TIM8_CH1/SDIO_D6/USART6_TX/DCMI_D0/TIM3_CH1/EVENTOUT_63") (pintype "bidirectional"))
    )
    (net (code "51") (name "/WATER") (class "Default")
      (node (ref "R6") (pin "1") (pinfunction "1_1") (pintype "passive"))
      (node (ref "U1") (pin "46") (pinfunction "PE15/FSMC_D12/TIM1_BKIN/EVENTOUT_46") (pintype "bidirectional"))
      (node (ref "U3") (pin "1") (pinfunction "OUT_1") (pintype "output"))
    )
    (net (code "52") (name "D_GND") (class "Default")
      (node (ref "P1") (pin "5") (pinfunction "5_5") (pintype "passive"))
      (node (ref "P1") (pin "6") (pinfunction "6_6") (pintype "passive"))
      (node (ref "P1") (pin "7") (pinfunction "7_7") (pintype "passive"))
      (node (ref "P1") (pin "8") (pinfunction "8_8") (pintype "passive"))
      (node (ref "Q1") (pin "3") (pinfunction "S_3") (pintype "passive"))
      (node (ref "Q2") (pin "3") (pinfunction "S_3") (pintype "passive"))
      (node (ref "Q3") (pin "2") (pinfunction "E_2") (pintype "passive"))
      (node (ref "Q4") (pin "2") (pinfunction "E_2") (pintype "passive"))
    )
    (net (code "53") (name "GND") (class "Default")
      (node (ref "C1") (pin "2") (pinfunction "2_2") (pintype "passive"))
      (node (ref "C10") (pin "1") (pinfunction "1_1") (pintype "passive"))
      (node (ref "C11") (pin "1") (pinfunction "1_1") (pintype "passive"))
      (node (ref "C13") (pin "2") (pinfunction "2_2") (pintype "passive"))
      (node (ref "C14") (pin "2") (pinfunction "2_2") (pintype "passive"))
      (node (ref "C15") (pin "1") (pinfunction "1_1") (pintype "passive"))
      (node (ref "C16") (pin "1") (pinfunction "1_1") (pintype "passive"))
      (node (ref "C17") (pin "2") (pinfunction "2_2") (pintype "passive"))
      (node (ref "C18") (pin "1") (pinfunction "1_1") (pintype "passive"))
      (node (ref "C19") (pin "1") (pinfunction "1_1") (pintype "passive"))
      (node (ref "C2") (pin "1") (pinfunction "1_1") (pintype "passive"))
      (node (ref "C3") (pin "1") (pinfunction "1_1") (pintype "passive"))
      (node (ref "C4") (pin "1") (pinfunction "1_1") (pintype "passive"))
      (node (ref "C5") (pin "2") (pinfunction "2_2") (pintype "passive"))
      (node (ref "C6") (pin "1") (pinfunction "1_1") (pintype "passive"))
      (node (ref "C7") (pin "1") (pinfunction "1_1") (pintype "passive"))
      (node (ref "C8") (pin "1") (pinfunction "1_1") (pintype "passive"))
      (node (ref "C9") (pin "1") (pinfunction "1_1") (pintype "passive"))
      (node (ref "P1") (pin "39") (pinfunction "39_39") (pintype "passive"))
      (node (ref "P1") (pin "40") (pinfunction "40_40") (pintype "passive"))
      (node (ref "P2") (pin "11") (pinfunction "11_11") (pintype "passive"))
      (node (ref "P2") (pin "12") (pinfunction "12_12") (pintype "passive"))
      (node (ref "P2") (pin "21") (pinfunction "21_21") (pintype "passive"))
      (node (ref "P2") (pin "22") (pinfunction "22_22") (pintype "passive"))
      (node (ref "P2") (pin "31") (pinfunction "31_31") (pintype "passive"))
      (node (ref "P2") (pin "32") (pinfunction "32_32") (pintype "passive"))
      (node (ref "P2") (pin "35") (pinfunction "35_35") (pintype "passive"))
      (node (ref "P2") (pin "7") (pinfunction "7_7") (pintype "passive"))
      (node (ref "P2") (pin "8") (pinfunction "8_8") (pintype "passive"))
      (node (ref "P3") (pin "4") (pinfunction "4_4") (pintype "passive"))
      (node (ref "R10") (pin "2") (pinfunction "2_2") (pintype "passive"))
      (node (ref "R2") (pin "2") (pinfunction "2_2") (pintype "passive"))
      (node (ref "R20") (pin "1") (pinfunction "1_1") (pintype "passive"))
      (node (ref "R23") (pin "1") (pinfunction "1_1") (pintype "passive"))
      (node (ref "R32") (pin "2") (pinfunction "2_2") (pintype "passive"))
      (node (ref "R33") (pin "2") (pinfunction "2_2") (pintype "passive"))
      (node (ref "R34") (pin "2") (pinfunction "2_2") (pintype "passive"))
      (node (ref "R35") (pin "2") (pinfunction "2_2") (pintype "passive"))
      (node (ref "R37") (pin "2") (pinfunction "2_2") (pintype "passive"))
      (node (ref "R7") (pin "1") (pinfunction "1_1") (pintype "passive"))
      (node (ref "S1") (pin "2") (pinfunction "2_2") (pintype "passive"))
      (node (ref "U1") (pin "10") (pinfunction "VSS_10") (pintype "power_in"))
      (node (ref "U1") (pin "27") (pinfunction "VSS_27") (pintype "power_in"))
      (node (ref "U1") (pin "74") (pinfunction "VSS_74") (pintype "power_in"))
      (node (ref "U1") (pin "99") (pinfunction "VSS_99") (pintype "power_in"))
      (node (ref "U2") (pin "2") (pinfunction "GND_2") (pintype "passive"))
      (node (ref "U3") (pin "4") (pinfunction "GND_4") (pintype "power_in"))
      (node (ref "U4") (pin "2") (pinfunction "GND_2") (pintype "passive"))
      (node (ref "U6") (pin "1") (pinfunction "VCC_1") (pintype "passive"))
      (node (ref "VR1") (pin "1") (pinfunction "GND_1") (pintype "passive"))
    )
    (net (code "54") (name "Net-(C2-Pad2)") (class "Default")
      (node (ref "C2") (pin "2") (pinfunction "2_2") (pintype "passive"))
      (node (ref "R9") (pin "1") (pinfunction "1_1") (pintype "passive"))
    )
    (net (code "55") (name "Net-(D1-PadK)") (class "Default")
      (node (ref "D1") (pin "K") (pinfunction "K_K") (pintype "passive"))
      (node (ref "R20") (pin "2") (pinfunction "2_2") (pintype "passive"))
    )
    (net (code "56") (name "Net-(D2-PadK)") (class "Default")
      (node (ref "D2") (pin "K") (pinfunction "K_K") (pintype "passive"))
      (node (ref "R33") (pin "1") (pinfunction "1_1") (pintype "passive"))
    )
    (net (code "57") (name "Net-(D3-PadK)") (class "Default")
      (node (ref "D3") (pin "K") (pinfunction "K_K") (pintype "passive"))
      (node (ref "R34") (pin "1") (pinfunction "1_1") (pintype "passive"))
    )
    (net (code "58") (name "Net-(D4-PadK)") (class "Default")
      (node (ref "D4") (pin "K") (pinfunction "K_K") (pintype "passive"))
      (node (ref "R36") (pin "2") (pinfunction "2_2") (pintype "passive"))
    )
    (net (code "59") (name "Net-(Q1-G)") (class "Default")
      (node (ref "Q1") (pin "1") (pinfunction "G_1") (pintype "passive"))
      (node (ref "Q3") (pin "3") (pinfunction "C_3") (pintype "passive"))
      (node (ref "R24") (pin "1") (pinfunction "1_1") (pintype "passive"))
    )
    (net (code "60") (name "Net-(Q2-G)") (class "Default")
      (node (ref "Q2") (pin "1") (pinfunction "G_1") (pintype "passive"))
      (node (ref "Q4") (pin "3") (pinfunction "C_3") (pintype "passive"))
      (node (ref "R25") (pin "1") (pinfunction "1_1") (pintype "passive"))
    )
    (net (code "61") (name "Net-(Q3-B)") (class "Default")
      (node (ref "Q3") (pin "1") (pinfunction "B_1") (pintype "passive"))
      (node (ref "R27") (pin "1") (pinfunction "1_1") (pintype "passive"))
      (node (ref "R29") (pin "2") (pinfunction "2_2") (pintype "passive"))
    )
    (net (code "62") (name "Net-(Q4-B)") (class "Default")
      (node (ref "Q4") (pin "1") (pinfunction "B_1") (pintype "passive"))
      (node (ref "R28") (pin "1") (pinfunction "1_1") (pintype "passive"))
      (node (ref "R30") (pin "2") (pinfunction "2_2") (pintype "passive"))
    )
    (net (code "63") (name "Net-(R1-Pad1)") (class "Default")
      (node (ref "R1") (pin "1") (pinfunction "1_1") (pintype "passive"))
      (node (ref "R3") (pin "2") (pinfunction "2_2") (pintype "passive"))
    )
    (net (code "64") (name "Net-(R11-Pad2)") (class "Default")
      (node (ref "R11") (pin "2") (pinfunction "2_2") (pintype "passive"))
      (node (ref "R8") (pin "1") (pinfunction "1_1") (pintype "passive"))
    )
    (net (code "65") (name "Net-(R14-Pad2)") (class "Default")
      (node (ref "R14") (pin "2") (pinfunction "2_2") (pintype "passive"))
      (node (ref "U5") (pin "2") (pinfunction "2_2") (pintype "passive"))
    )
    (net (code "66") (name "Net-(R16-Pad2)") (class "Default")
      (node (ref "R16") (pin "2") (pinfunction "2_2") (pintype "passive"))
      (node (ref "U5") (pin "4") (pinfunction "4_4") (pintype "passive"))
    )
    (net (code "67") (name "Net-(R18-Pad2)") (class "Default")
      (node (ref "R18") (pin "2") (pinfunction "2_2") (pintype "passive"))
      (node (ref "U5") (pin "6") (pinfunction "6_6") (pintype "passive"))
    )
    (net (code "68") (name "Net-(R21-Pad2)") (class "Default")
      (node (ref "R21") (pin "2") (pinfunction "2_2") (pintype "passive"))
      (node (ref "U5") (pin "8") (pinfunction "8_8") (pintype "passive"))
    )
    (net (code "69") (name "Net-(R35-Pad1)") (class "Default")
      (node (ref "R35") (pin "1") (pinfunction "1_1") (pintype "passive"))
      (node (ref "S2") (pin "2") (pinfunction "2_2") (pintype "passive"))
    )
    (net (code "70") (name "Net-(U1D-BOOT0{slash}VPP)") (class "Default")
      (node (ref "R32") (pin "1") (pinfunction "1_1") (pintype "passive"))
      (node (ref "U1") (pin "94") (pinfunction "BOOT0/VPP_94") (pintype "input"))
    )
    (net (code "71") (name "Net-(U1D-NRST)") (class "Default")
      (node (ref "C19") (pin "2") (pinfunction "2_2") (pintype "passive"))
      (node (ref "R31") (pin "1") (pinfunction "1_1") (pintype "passive"))
      (node (ref "S1") (pin "1") (pinfunction "1_1") (pintype "passive"))
      (node (ref "U1") (pin "14") (pinfunction "NRST_14") (pintype "bidirectional"))
    )
    (net (code "72") (name "Net-(U1D-PH0-OSC_IN(PH0){slash}EVENTOUT{slash}OSC_IN)") (class "Default")
      (node (ref "C18") (pin "2") (pinfunction "2_2") (pintype "passive"))
      (node (ref "U1") (pin "12") (pinfunction "PH0-OSC_IN(PH0)/EVENTOUT/OSC_IN_12") (pintype "bidirectional"))
      (node (ref "Y1") (pin "1") (pinfunction "OSC1_1") (pintype "passive"))
    )
    (net (code "73") (name "Net-(U1D-PH1-OSC_OUT(PH1){slash}EVENTOUT{slash}OSC_OUT)") (class "Default")
      (node (ref "C16") (pin "2") (pinfunction "2_2") (pintype "passive"))
      (node (ref "U1") (pin "13") (pinfunction "PH1-OSC_OUT(PH1)/EVENTOUT/OSC_OUT_13") (pintype "bidirectional"))
      (node (ref "Y1") (pin "2") (pinfunction "OSC2_2") (pintype "passive"))
    )
    (net (code "74") (name "Net-(U1D-VCAP_1)") (class "Default")
      (node (ref "C17") (pin "1") (pinfunction "1_1") (pintype "passive"))
      (node (ref "U1") (pin "49") (pinfunction "VCAP_1_49") (pintype "power_in"))
    )
    (net (code "75") (name "Net-(U1D-VCAP_2)") (class "Default")
      (node (ref "C15") (pin "2") (pinfunction "2_2") (pintype "passive"))
      (node (ref "U1") (pin "73") (pinfunction "VCAP_2_73") (pintype "power_in"))
    )
    (net (code "76") (name "Net-(U1E-VDDA)") (class "Default")
      (node (ref "C12") (pin "1") (pinfunction "1_1") (pintype "passive"))
      (node (ref "R22") (pin "2") (pinfunction "2_2") (pintype "passive"))
      (node (ref "U1") (pin "22") (pinfunction "VDDA_22") (pintype "power_in"))
    )
    (net (code "77") (name "Net-(U1E-VSSA)") (class "Default")
      (node (ref "C12") (pin "2") (pinfunction "2_2") (pintype "passive"))
      (node (ref "R23") (pin "2") (pinfunction "2_2") (pintype "passive"))
      (node (ref "U1") (pin "20") (pinfunction "VSSA_20") (pintype "power_in"))
    )
    (net (code "78") (name "Net-(U2-RS)") (class "Default")
      (node (ref "R2") (pin "1") (pinfunction "1_1") (pintype "passive"))
      (node (ref "U2") (pin "8") (pinfunction "RS_8") (pintype "passive"))
    )
    (net (code "79") (name "Net-(U2-VCC)") (class "Default")
      (node (ref "R4") (pin "2") (pinfunction "2_2") (pintype "passive"))
      (node (ref "U2") (pin "3") (pinfunction "VCC_3") (pintype "passive"))
    )
    (net (code "80") (name "Net-(U3A-IN-)") (class "Default")
      (node (ref "R5") (pin "1") (pinfunction "1_1") (pintype "passive"))
      (node (ref "R7") (pin "2") (pinfunction "2_2") (pintype "passive"))
      (node (ref "U3") (pin "2") (pinfunction "IN-_2") (pintype "input"))
    )
    (net (code "81") (name "Net-(U4-RS)") (class "Default")
      (node (ref "R10") (pin "1") (pinfunction "1_1") (pintype "passive"))
      (node (ref "U4") (pin "8") (pinfunction "RS_8") (pintype "passive"))
    )
    (net (code "82") (name "Net-(U4-VCC)") (class "Default")
      (node (ref "R12") (pin "2") (pinfunction "2_2") (pintype "passive"))
      (node (ref "U4") (pin "3") (pinfunction "VCC_3") (pintype "passive"))
    )
    (net (code "83") (name "POWER_LED1_GND") (class "Default")
      (node (ref "P1") (pin "13") (pinfunction "13_13") (pintype "passive"))
      (node (ref "P1") (pin "14") (pinfunction "14_14") (pintype "passive"))
      (node (ref "P1") (pin "15") (pinfunction "15_15") (pintype "passive"))
      (node (ref "P1") (pin "16") (pinfunction "16_16") (pintype "passive"))
      (node (ref "Q1") (pin "2") (pinfunction "D_2") (pintype "passive"))
    )
    (net (code "84") (name "POWER_LED1_VCC") (class "Default")
      (node (ref "P1") (pin "1") (pinfunction "1_1") (pintype "passive"))
      (node (ref "P1") (pin "10") (pinfunction "10_10") (pintype "passive"))
      (node (ref "P1") (pin "11") (pinfunction "11_11") (pintype "passive"))
      (node (ref "P1") (pin "12") (pinfunction "12_12") (pintype "passive"))
      (node (ref "P1") (pin "17") (pinfunction "17_17") (pintype "passive"))
      (node (ref "P1") (pin "18") (pinfunction "18_18") (pintype "passive"))
      (node (ref "P1") (pin "19") (pinfunction "19_19") (pintype "passive"))
      (node (ref "P1") (pin "2") (pinfunction "2_2") (pintype "passive"))
      (node (ref "P1") (pin "20") (pinfunction "20_20") (pintype "passive"))
      (node (ref "P1") (pin "3") (pinfunction "3_3") (pintype "passive"))
      (node (ref "P1") (pin "4") (pinfunction "4_4") (pintype "passive"))
      (node (ref "P1") (pin "9") (pinfunction "9_9") (pintype "passive"))
      (node (ref "R24") (pin "2") (pinfunction "2_2") (pintype "passive"))
      (node (ref "R25") (pin "2") (pinfunction "2_2") (pintype "passive"))
    )
    (net (code "85") (name "POWER_LED2_GND") (class "Default")
      (node (ref "P1") (pin "21") (pinfunction "21_21") (pintype "passive"))
      (node (ref "P1") (pin "22") (pinfunction "22_22") (pintype "passive"))
      (node (ref "P1") (pin "23") (pinfunction "23_23") (pintype "passive"))
      (node (ref "P1") (pin "24") (pinfunction "24_24") (pintype "passive"))
      (node (ref "Q2") (pin "2") (pinfunction "D_2") (pintype "passive"))
    )
    (net (code "86") (name "PWM_5V") (class "Default")
      (node (ref "D4") (pin "A") (pinfunction "A_A") (pintype "passive"))
      (node (ref "P2") (pin "41") (pinfunction "41_41") (pintype "passive"))
      (node (ref "P2") (pin "42") (pinfunction "42_42") (pintype "passive"))
      (node (ref "R13") (pin "2") (pinfunction "2_2") (pintype "passive"))
      (node (ref "R15") (pin "2") (pinfunction "2_2") (pintype "passive"))
      (node (ref "R17") (pin "2") (pinfunction "2_2") (pintype "passive"))
      (node (ref "R19") (pin "2") (pinfunction "2_2") (pintype "passive"))
    )
    (net (code "87") (name "PWM_GND") (class "Default")
      (node (ref "P2") (pin "43") (pinfunction "43_43") (pintype "passive"))
      (node (ref "P2") (pin "44") (pinfunction "44_44") (pintype "passive"))
      (node (ref "R36") (pin "1") (pinfunction "1_1") (pintype "passive"))
      (node (ref "U5") (pin "11") (pinfunction "11_11") (pintype "passive"))
      (node (ref "U5") (pin "13") (pinfunction "13_13") (pintype "passive"))
      (node (ref "U5") (pin "15") (pinfunction "15_15") (pintype "passive"))
      (node (ref "U5") (pin "9") (pinfunction "9_9") (pintype "passive"))
    )
    (net (code "88") (name "VCC3.3") (class "Default")
      (node (ref "C1") (pin "1") (pinfunction "1_1") (pintype "passive"))
      (node (ref "C10") (pin "2") (pinfunction "2_2") (pintype "passive"))
      (node (ref "C11") (pin "2") (pinfunction "2_2") (pintype "passive"))
      (node (ref "C13") (pin "1") (pinfunction "1_1") (pintype "passive"))
      (node (ref "C14") (pin "1") (pinfunction "1_1") (pintype "passive"))
      (node (ref "C3") (pin "2") (pinfunction "2_2") (pintype "passive"))
      (node (ref "C4") (pin "2") (pinfunction "2_2") (pintype "passive"))
      (node (ref "C5") (pin "1") (pinfunction "1_1") (pintype "passive"))
      (node (ref "C8") (pin "2") (pinfunction "2_2") (pintype "passive"))
      (node (ref "C9") (pin "2") (pinfunction "2_2") (pintype "passive"))
      (node (ref "D1") (pin "A") (pinfunction "A_A") (pintype "passive"))
      (node (ref "P1") (pin "43") (pinfunction "43_43") (pintype "passive"))
      (node (ref "P1") (pin "44") (pinfunction "44_44") (pintype "passive"))
      (node (ref "P2") (pin "13") (pinfunction "13_13") (pintype "passive"))
      (node (ref "P2") (pin "14") (pinfunction "14_14") (pintype "passive"))
      (node (ref "P2") (pin "25") (pinfunction "25_25") (pintype "passive"))
      (node (ref "P2") (pin "26") (pinfunction "26_26") (pintype "passive"))
      (node (ref "P3") (pin "1") (pinfunction "1_1") (pintype "passive"))
      (node (ref "R12") (pin "1") (pinfunction "1_1") (pintype "passive"))
      (node (ref "R22") (pin "1") (pinfunction "1_1") (pintype "passive"))
      (node (ref "R26") (pin "2") (pinfunction "2_2") (pintype "passive"))
      (node (ref "R27") (pin "2") (pinfunction "2_2") (pintype "passive"))
      (node (ref "R28") (pin "2") (pinfunction "2_2") (pintype "passive"))
      (node (ref "R31") (pin "2") (pinfunction "2_2") (pintype "passive"))
      (node (ref "R4") (pin "1") (pinfunction "1_1") (pintype "passive"))
      (node (ref "R5") (pin "2") (pinfunction "2_2") (pintype "passive"))
      (node (ref "R6") (pin "2") (pinfunction "2_2") (pintype "passive"))
      (node (ref "R9") (pin "2") (pinfunction "2_2") (pintype "passive"))
      (node (ref "U1") (pin "100") (pinfunction "VDD_100") (pintype "power_in"))
      (node (ref "U1") (pin "11") (pinfunction "VDD_11") (pintype "power_in"))
      (node (ref "U1") (pin "19") (pinfunction "VDD_19") (pintype "power_in"))
      (node (ref "U1") (pin "21") (pinfunction "VREF+_21") (pintype "power_in"))
      (node (ref "U1") (pin "28") (pinfunction "VDD_28") (pintype "power_in"))
      (node (ref "U1") (pin "50") (pinfunction "VDD_50") (pintype "power_in"))
      (node (ref "U1") (pin "6") (pinfunction "VBAT_6") (pintype "power_in"))
      (node (ref "U1") (pin "75") (pinfunction "VDD_75") (pintype "power_in"))
      (node (ref "U3") (pin "8") (pinfunction "V+_8") (pintype "power_in"))
      (node (ref "U5") (pin "1") (pinfunction "1_1") (pintype "passive"))
      (node (ref "U5") (pin "3") (pinfunction "3_3") (pintype "passive"))
      (node (ref "U5") (pin "5") (pinfunction "5_5") (pintype "passive"))
      (node (ref "U5") (pin "7") (pinfunction "7_7") (pintype "passive"))
      (node (ref "U6") (pin "3") (pinfunction "GND_3") (pintype "passive"))
      (node (ref "VR1") (pin "2") (pinfunction "Vout_2") (pintype "passive"))
    )
    (net (code "89") (name "VCC5") (class "Default")
      (node (ref "C6") (pin "2") (pinfunction "2_2") (pintype "passive"))
      (node (ref "C7") (pin "2") (pinfunction "2_2") (pintype "passive"))
      (node (ref "P2") (pin "1") (pinfunction "1_1") (pintype "passive"))
      (node (ref "P2") (pin "10") (pinfunction "10_10") (pintype "passive"))
      (node (ref "P2") (pin "15") (pinfunction "15_15") (pintype "passive"))
      (node (ref "P2") (pin "16") (pinfunction "16_16") (pintype "passive"))
      (node (ref "P2") (pin "2") (pinfunction "2_2") (pintype "passive"))
      (node (ref "P2") (pin "23") (pinfunction "23_23") (pintype "passive"))
      (node (ref "P2") (pin "24") (pinfunction "24_24") (pintype "passive"))
      (node (ref "P2") (pin "9") (pinfunction "9_9") (pintype "passive"))
      (node (ref "VR1") (pin "3") (pinfunction "Vin_3") (pintype "passive"))
    )
    (net (code "90") (name "unconnected-(U1A-PA0-WKUP(PA0){slash}USART2_CTS{slash}UART4_TX{slash}ETH_MII_CRS{slash}TIM2_CH1_ETR{slash}TIM5_CH1{slash}TIM8_ETR{slash}EVENTOUT{slash}ADC123_IN0{slash}WKUP-Pad23)") (class "Default")
      (node (ref "U1") (pin "23") (pinfunction "PA0-WKUP(PA0)/USART2_CTS/UART4_TX/ETH_MII_CRS/TIM2_CH1_ETR/TIM5_CH1/TIM8_ETR/EVENTOUT/ADC123_IN0/WKUP_23") (pintype "bidirectional"))
    )
    (net (code "91") (name "unconnected-(U1A-PA5{slash}SPI1_SCK{slash}OTG_HS_ULPI_CK{slash}TIM2_CH1_ETR{slash}TIM8_CHIN{slash}EVENTOUT{slash}ADC12_IN5{slash}DAC2_OUT-Pad30)") (class "Default")
      (node (ref "U1") (pin "30") (pinfunction "PA5/SPI1_SCK/OTG_HS_ULPI_CK/TIM2_CH1_ETR/TIM8_CHIN/EVENTOUT/ADC12_IN5/DAC2_OUT_30") (pintype "bidirectional"))
    )
    (net (code "92") (name "unconnected-(U1A-PA6{slash}SPI1_MISO{slash}TIM8_BKIN{slash}TIM13_CH1{slash}DCMI_PIXCLK{slash}TIM3_CH1{slash}TIM1_BKIN{slash}EVENTOUT{slash}ADC12_IN6-Pad31)") (class "Default")
      (node (ref "U1") (pin "31") (pinfunction "PA6/SPI1_MISO/TIM8_BKIN/TIM13_CH1/DCMI_PIXCLK/TIM3_CH1/TIM1_BKIN/EVENTOUT/ADC12_IN6_31") (pintype "bidirectional"))
    )
    (net (code "93") (name "unconnected-(U1A-PA7{slash}SPI1_MOSI{slash}TIM8_CH1N{slash}TIM14_CH1{slash}TIM3_CH2{slash}ETH_MII_RX_DV{slash}TIM1_CH1N{slash}RMII_CRS_DV{slash}EVENTOUT{slash}ADC12_IN7-Pad32)") (class "Default")
      (node (ref "U1") (pin "32") (pinfunction "PA7/SPI1_MOSI/TIM8_CH1N/TIM14_CH1/TIM3_CH2/ETH_MII_RX_DV/TIM1_CH1N/RMII_CRS_DV/EVENTOUT/ADC12_IN7_32") (pintype "bidirectional"))
    )
    (net (code "94") (name "unconnected-(U1A-PA8{slash}MCO1{slash}USART1_CK{slash}TIM1_CH1{slash}I2C3_SCL{slash}OTG_FS_SOF{slash}EVENTOUT-Pad67)") (class "Default")
      (node (ref "U1") (pin "67") (pinfunction "PA8/MCO1/USART1_CK/TIM1_CH1/I2C3_SCL/OTG_FS_SOF/EVENTOUT_67") (pintype "bidirectional"))
    )
    (net (code "95") (name "unconnected-(U1A-PA12{slash}USART1_RTS{slash}CAN1_TX{slash}TIM1_ETR{slash}OTG_FS_DP{slash}EVENTOUT-Pad71)") (class "Default")
      (node (ref "U1") (pin "71") (pinfunction "PA12/USART1_RTS/CAN1_TX/TIM1_ETR/OTG_FS_DP/EVENTOUT_71") (pintype "bidirectional"))
    )
    (net (code "96") (name "unconnected-(U1A-PA15(JTDI){slash}JTDI{slash}SPI3_NSS{slash}I2S3_WS{slash}TIM2_CH1_ETR{slash}SPI1_NSS{slash}EVENTOUT-Pad77)") (class "Default")
      (node (ref "U1") (pin "77") (pinfunction "PA15(JTDI)/JTDI/SPI3_NSS/I2S3_WS/TIM2_CH1_ETR/SPI1_NSS/EVENTOUT_77") (pintype "bidirectional"))
    )
    (net (code "97") (name "unconnected-(U1A-PB0{slash}TIM3_CH3{slash}TIM8_CH2N{slash}OTG_HS_ULPI_D1{slash}ETH_MII_RXD2{slash}TIM1_CH2N{slash}EVENTOUT{slash}ADC12_IN8-Pad35)") (class "Default")
      (node (ref "U1") (pin "35") (pinfunction "PB0/TIM3_CH3/TIM8_CH2N/OTG_HS_ULPI_D1/ETH_MII_RXD2/TIM1_CH2N/EVENTOUT/ADC12_IN8_35") (pintype "bidirectional"))
    )
    (net (code "98") (name "unconnected-(U1A-PB1{slash}TIM3_CH4{slash}TIM8_CH3N{slash}OTG_HS_ULPI_D2{slash}ETH_MII_RXD3{slash}OTG_HS_INTN{slash}TIM1_CH3N{slash}EVENTOUT{slash}ADC12_IN9-Pad36)") (class "Default")
      (node (ref "U1") (pin "36") (pinfunction "PB1/TIM3_CH4/TIM8_CH3N/OTG_HS_ULPI_D2/ETH_MII_RXD3/OTG_HS_INTN/TIM1_CH3N/EVENTOUT/ADC12_IN9_36") (pintype "bidirectional"))
    )
    (net (code "99") (name "unconnected-(U1A-PB12{slash}SPI2_NSS{slash}I2S2_WS{slash}I2C2_SMBA{slash}USART3_CK{slash}TIM1_BKIN{slash}CAN2_RX{slash}OTG_HS_ULPI_D5{slash}ETH_RMII_TXD0{slash}ETH_MII_TXD0{slash}OTG_HS_ID{slash}EVENTOUT-Pad51)") (class "Default")
      (node (ref "U1") (pin "51") (pinfunction "PB12/SPI2_NSS/I2S2_WS/I2C2_SMBA/USART3_CK/TIM1_BKIN/CAN2_RX/OTG_HS_ULPI_D5/ETH_RMII_TXD0/ETH_MII_TXD0/OTG_HS_ID/EVENTOUT_51") (pintype "bidirectional"))
    )
    (net (code "100") (name "unconnected-(U1A-PB13{slash}SPI2_SCK{slash}I2S2_CK{slash}USART3_CTS{slash}TIM1_CH1N{slash}CAN2_TX{slash}OTG_HS_ULPI_D6{slash}ETH_RMII_TXD1{slash}ETH_MII_TXD1{slash}EVENTOUT{slash}OTG_HS_VBUS-Pad52)") (class "Default")
      (node (ref "U1") (pin "52") (pinfunction "PB13/SPI2_SCK/I2S2_CK/USART3_CTS/TIM1_CH1N/CAN2_TX/OTG_HS_ULPI_D6/ETH_RMII_TXD1/ETH_MII_TXD1/EVENTOUT/OTG_HS_VBUS_52") (pintype "bidirectional"))
    )
    (net (code "101") (name "unconnected-(U1A-PB14{slash}SPI2_MISO{slash}TIM1_CH2N{slash}TIM12_CH1{slash}OTG_HS_DM{slash}USART3_RTS{slash}TIM8_CH2N{slash}I2S2ext_SD{slash}EVENTOUT-Pad53)") (class "Default")
      (node (ref "U1") (pin "53") (pinfunction "PB14/SPI2_MISO/TIM1_CH2N/TIM12_CH1/OTG_HS_DM/USART3_RTS/TIM8_CH2N/I2S2ext_SD/EVENTOUT_53") (pintype "bidirectional"))
    )
    (net (code "102") (name "unconnected-(U1A-PB15{slash}SPI2_MOSI{slash}I2S2_SD{slash}TIM1_CH3N{slash}TIM8_CH3N{slash}TIM12_CH2{slash}OTG_HS_DP{slash}EVENTOUT-Pad54)") (class "Default")
      (node (ref "U1") (pin "54") (pinfunction "PB15/SPI2_MOSI/I2S2_SD/TIM1_CH3N/TIM8_CH3N/TIM12_CH2/OTG_HS_DP/EVENTOUT_54") (pintype "bidirectional"))
    )
    (net (code "103") (name "unconnected-(U1B-PC1{slash}ETH_MDC{slash}EVENTOUT{slash}ADC123_IN11-Pad16)") (class "Default")
      (node (ref "U1") (pin "16") (pinfunction "PC1/ETH_MDC/EVENTOUT/ADC123_IN11_16") (pintype "bidirectional"))
    )
    (net (code "104") (name "unconnected-(U1B-PC2{slash}SPI2_MISO{slash}OTG_HS_ULPI_DIR{slash}TH_MII_TXD2{slash}I2S2ext_SD{slash}EVENTOUT{slash}ADC123_IN12-Pad17)") (class "Default")
      (node (ref "U1") (pin "17") (pinfunction "PC2/SPI2_MISO/OTG_HS_ULPI_DIR/TH_MII_TXD2/I2S2ext_SD/EVENTOUT/ADC123_IN12_17") (pintype "bidirectional"))
    )
    (net (code "105") (name "unconnected-(U1B-PC3{slash}SPI2_MOSI{slash}I2S2_SD{slash}OTG_HS_ULPI_NXT{slash}ETH_MII_TX_CLK{slash}EVENTOUT{slash}ADC123_IN13-Pad18)") (class "Default")
      (node (ref "U1") (pin "18") (pinfunction "PC3/SPI2_MOSI/I2S2_SD/OTG_HS_ULPI_NXT/ETH_MII_TX_CLK/EVENTOUT/ADC123_IN13_18") (pintype "bidirectional"))
    )
    (net (code "106") (name "unconnected-(U1B-PC4{slash}ETH_RMII_RX_D0{slash}ETH_MII_RX_D0{slash}EVENTOUT{slash}ADC12_IN14-Pad33)") (class "Default")
      (node (ref "U1") (pin "33") (pinfunction "PC4/ETH_RMII_RX_D0/ETH_MII_RX_D0/EVENTOUT/ADC12_IN14_33") (pintype "bidirectional"))
    )
    (net (code "107") (name "unconnected-(U1B-PC5{slash}ETH_RMII_RX_D1{slash}ETH_MII_RX_D1{slash}EVENTOUT{slash}ADC12_IN15-Pad34)") (class "Default")
      (node (ref "U1") (pin "34") (pinfunction "PC5/ETH_RMII_RX_D1/ETH_MII_RX_D1/EVENTOUT/ADC12_IN15_34") (pintype "bidirectional"))
    )
    (net (code "108") (name "unconnected-(U1B-PC8{slash}TIM8_CH3{slash}SDIO_D0{slash}TIM3_CH3{slash}USART6_CK{slash}DCMI_D2{slash}EVENTOUT-Pad65)") (class "Default")
      (node (ref "U1") (pin "65") (pinfunction "PC8/TIM8_CH3/SDIO_D0/TIM3_CH3/USART6_CK/DCMI_D2/EVENTOUT_65") (pintype "bidirectional"))
    )
    (net (code "109") (name "unconnected-(U1B-PC9{slash}I2S_CKIN{slash}MCO2{slash}TIM8_CH4{slash}SDIO_D1{slash}{slash}I2C3_SDA{slash}DCMI_D3{slash}TIM3_CH4{slash}EVENTOUT-Pad66)") (class "Default")
      (node (ref "U1") (pin "66") (pinfunction "PC9/I2S_CKIN/MCO2/TIM8_CH4/SDIO_D1//I2C3_SDA/DCMI_D3/TIM3_CH4/EVENTOUT_66") (pintype "bidirectional"))
    )
    (net (code "110") (name "unconnected-(U1B-PC10{slash}SPI3_SCK{slash}I2S3_CK{slash}UART4_TX{slash}SDIO_D2{slash}DCMI_D8{slash}USART3_TX{slash}EVENTOUT-Pad78)") (class "Default")
      (node (ref "U1") (pin "78") (pinfunction "PC10/SPI3_SCK/I2S3_CK/UART4_TX/SDIO_D2/DCMI_D8/USART3_TX/EVENTOUT_78") (pintype "bidirectional"))
    )
    (net (code "111") (name "unconnected-(U1B-PC11{slash}UART4_RX{slash}SPI3_MISO{slash}SDIO_D3{slash}DCMI_D4{slash}USART3_RX{slash}I2S3ext_SD{slash}EVENTOUT-Pad79)") (class "Default")
      (node (ref "U1") (pin "79") (pinfunction "PC11/UART4_RX/SPI3_MISO/SDIO_D3/DCMI_D4/USART3_RX/I2S3ext_SD/EVENTOUT_79") (pintype "bidirectional"))
    )
    (net (code "112") (name "unconnected-(U1B-PC12{slash}UART5_TX{slash}SDIO_CK{slash}DCMI_D9{slash}SPI3_MOSI{slash}I2S3_SD{slash}USART3_CK{slash}EVENTOUT-Pad80)") (class "Default")
      (node (ref "U1") (pin "80") (pinfunction "PC12/UART5_TX/SDIO_CK/DCMI_D9/SPI3_MOSI/I2S3_SD/USART3_CK/EVENTOUT_80") (pintype "bidirectional"))
    )
    (net (code "113") (name "unconnected-(U1B-PC14-OSC32_IN(PC14){slash}EVENTOUT{slash}OSC32_IN-Pad8)") (class "Default")
      (node (ref "U1") (pin "8") (pinfunction "PC14-OSC32_IN(PC14)/EVENTOUT/OSC32_IN_8") (pintype "bidirectional"))
    )
    (net (code "114") (name "unconnected-(U1B-PC15-OSC32_OUT(PC15){slash}EVENTOUT{slash}OSC32_OUT-Pad9)") (class "Default")
      (node (ref "U1") (pin "9") (pinfunction "PC15-OSC32_OUT(PC15)/EVENTOUT/OSC32_OUT_9") (pintype "bidirectional"))
    )
    (net (code "115") (name "unconnected-(U1B-PD2{slash}TIM3_ETR{slash}UART5_RX{slash}SDIO_CMD{slash}DCMI_D11{slash}EVENTOUT-Pad83)") (class "Default")
      (node (ref "U1") (pin "83") (pinfunction "PD2/TIM3_ETR/UART5_RX/SDIO_CMD/DCMI_D11/EVENTOUT_83") (pintype "bidirectional"))
    )
    (net (code "116") (name "unconnected-(U1B-PD3{slash}FSMC_CLK{slash}USART2_CTS{slash}EVENTOUT-Pad84)") (class "Default")
      (node (ref "U1") (pin "84") (pinfunction "PD3/FSMC_CLK/USART2_CTS/EVENTOUT_84") (pintype "bidirectional"))
    )
    (net (code "117") (name "unconnected-(U1B-PD4{slash}FSMC_NOE{slash}USART2_RTS{slash}EVENTOUT-Pad85)") (class "Default")
      (node (ref "U1") (pin "85") (pinfunction "PD4/FSMC_NOE/USART2_RTS/EVENTOUT_85") (pintype "bidirectional"))
    )
    (net (code "118") (name "unconnected-(U1B-PD5{slash}FSMC_NWE{slash}USART2_TX{slash}EVENTOUT-Pad86)") (class "Default")
      (node (ref "U1") (pin "86") (pinfunction "PD5/FSMC_NWE/USART2_TX/EVENTOUT_86") (pintype "bidirectional"))
    )
    (net (code "119") (name "unconnected-(U1B-PD6{slash}FSMC_NWAIT{slash}USART2_RX{slash}EVENTOUT-Pad87)") (class "Default")
      (node (ref "U1") (pin "87") (pinfunction "PD6/FSMC_NWAIT/USART2_RX/EVENTOUT_87") (pintype "bidirectional"))
    )
    (net (code "120") (name "unconnected-(U1B-PD8{slash}FSMC_D13{slash}USART3_TX{slash}EVENTOUT-Pad55)") (class "Default")
      (node (ref "U1") (pin "55") (pinfunction "PD8/FSMC_D13/USART3_TX/EVENTOUT_55") (pintype "bidirectional"))
    )
    (net (code "121") (name "unconnected-(U1B-PD9{slash}FSMC_D14{slash}USART3_RX{slash}EVENTOUT-Pad56)") (class "Default")
      (node (ref "U1") (pin "56") (pinfunction "PD9/FSMC_D14/USART3_RX/EVENTOUT_56") (pintype "bidirectional"))
    )
    (net (code "122") (name "unconnected-(U1B-PD10{slash}FSMC_D15{slash}USART3_CK{slash}EVENTOUT-Pad57)") (class "Default")
      (node (ref "U1") (pin "57") (pinfunction "PD10/FSMC_D15/USART3_CK/EVENTOUT_57") (pintype "bidirectional"))
    )
    (net (code "123") (name "unconnected-(U1B-PD11{slash}FSMC_CLE{slash}FSMC_A16{slash}USART3_CTS{slash}EVENTOUT-Pad58)") (class "Default")
      (node (ref "U1") (pin "58") (pinfunction "PD11/FSMC_CLE/FSMC_A16/USART3_CTS/EVENTOUT_58") (pintype "bidirectional"))
    )
    (net (code "124") (name "unconnected-(U1C-PE7{slash}FSMC_D4{slash}TIM1_ETR{slash}EVENTOUT-Pad38)") (class "Default")
      (node (ref "U1") (pin "38") (pinfunction "PE7/FSMC_D4/TIM1_ETR/EVENTOUT_38") (pintype "bidirectional"))
    )
    (net (code "125") (name "unconnected-(U1C-PE8{slash}FSMC_D5{slash}TIM1_CH1N{slash}EVENTOUT-Pad39)") (class "Default")
      (node (ref "U1") (pin "39") (pinfunction "PE8/FSMC_D5/TIM1_CH1N/EVENTOUT_39") (pintype "bidirectional"))
    )
    (net (code "126") (name "unconnected-(U1C-PE9{slash}FSMC_D6{slash}TIM1_CH1{slash}EVENTOUT-Pad40)") (class "Default")
      (node (ref "U1") (pin "40") (pinfunction "PE9/FSMC_D6/TIM1_CH1/EVENTOUT_40") (pintype "bidirectional"))
    )
    (net (code "127") (name "unconnected-(U1C-PE14{slash}FSMC_D11{slash}TIM1_CH4{slash}EVENTOUT-Pad45)") (class "Default")
      (node (ref "U1") (pin "45") (pinfunction "PE14/FSMC_D11/TIM1_CH4/EVENTOUT_45") (pintype "bidirectional"))
    )
    (net (code "128") (name "unconnected-(U2-Vref-Pad5)") (class "Default")
      (node (ref "U2") (pin "5") (pinfunction "Vref_5") (pintype "passive+no_connect"))
    )
    (net (code "129") (name "unconnected-(U4-Vref-Pad5)") (class "Default")
      (node (ref "U4") (pin "5") (pinfunction "Vref_5") (pintype "passive+no_connect"))
    )
  )
)
